# Sheet2.net
KiCad netlist of a schematic drawn in Altium Designer
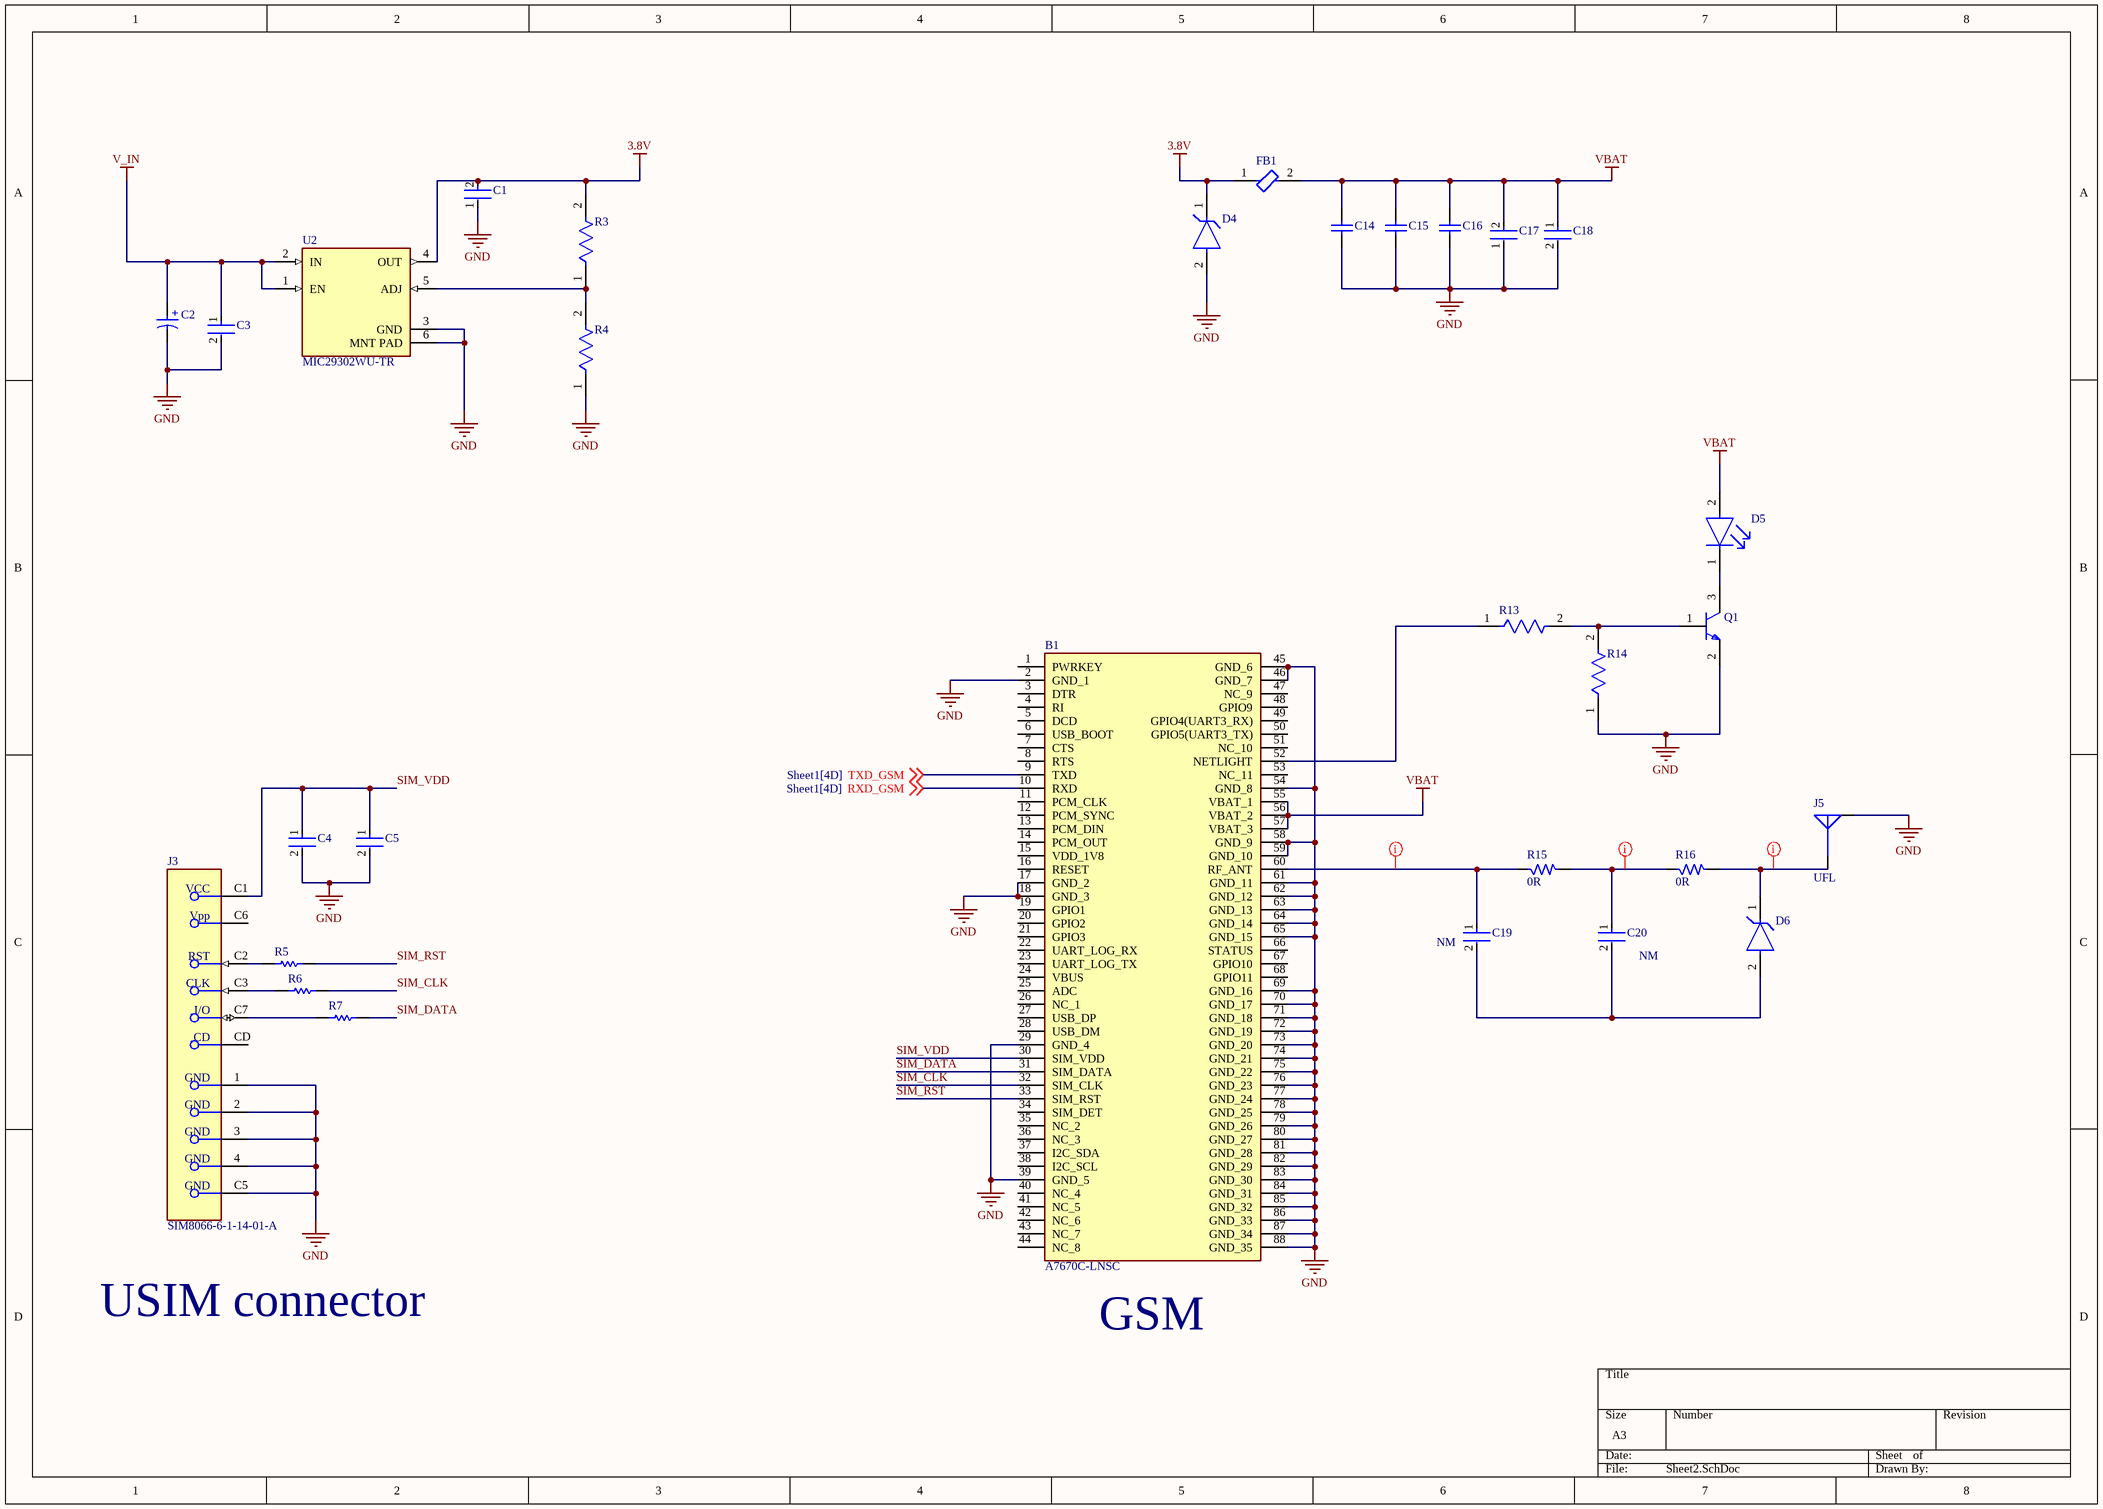
[diagram p0: Sheet2.SchDoc]

(export (version "E")
  (design (tool "Eeschema 10.0.6"))
  (components
    (comp (ref "B1")
      (value "A7670C-LNSC")
      (footprint "A7670CLNSC")
      (description "MODULE LTE CAT1")
      (libsource (lib "A7670C-LNSC") (part "A7670C-LNSC"))
    )
    (comp (ref "C1")
      (value "GRM155R71C104KA88D")
      (footprint "FP-GRM15-MFG")
      (description "CAP CER 0.1UF 16V X7R 0402")
      (fields
        (field (name "TOLERANCE") "10%")
        (field (name "OCTOPART") "https://octopart.com/grm155r71c104ka88d-murata-196880")
      )
      (libsource (lib "Altium Content Vault") (part "236180d848d6139a670b325ea6854c9"))
    )
    (comp (ref "C2")
      (value "865060653010")
      (footprint "WCAP-ASLL_D8H10.5")
      (fields (field (name "TOLERANCE") "20%"))
      (libsource (lib "Altium Content Vault") (part "Capacitor_Polarized"))
    )
    (comp (ref "C3")
      (value "C0402C105K8PACTU")
      (footprint "FP-C0402C105K8PACTU-MFG")
      (description "CAP CER 1UF 10V X5R 0402")
      (fields (field (name "VOLTAGE") "10V") (field (name "TOLERANCE") "10%"))
      (libsource (lib "Altium Content Vault") (part "11868f565c42a9108669ba33697ecf6"))
    )
    (comp (ref "C4")
      (value "C0402C104K4RACTU")
      (footprint "FP-C0402-BB-MFG")
      (description "CAP CER 0.1UF 16V X7R 0402")
      (fields
        (field (name "TOLERANCE") "0.1")
        (field (name "OCTOPART") "https://octopart.com/c0402c104k4ractu-kemet-94158")
      )
      (libsource (lib "Altium Content Vault") (part "b4654b650e69147ec39a6b967a45e02"))
    )
    (comp (ref "C5")
      (value "04025A330JAT2A")
      (footprint "FP-0402-L_1_0_1-W_0_5_0_1-IPC_A")
      (description "General Purpose Ceramic Capacitor, 0402, 33pF, 5%, C0G, 30ppm/°C, 50V")
      (fields (field (name "TOLERANCE") "5%") (field (name "VOLTAGE") "50V"))
      (libsource (lib "Altium Content Vault") (part "b4654b650e69147ec39a6b967a45e02"))
    )
    (comp (ref "C14")
      (value "GRM31CR60J107ME39L")
      (footprint "CAPC3216X190X55ML30T25")
      (description "Chip Capacitor, 100 uF, +/- 20%, 6.3 V, -55 to 85 degC, 1206 (3216 Metric), RoHS, Tape and Reel")
      (fields (field (name "TOLERANCE") "20%"))
      (libsource (lib "Altium Content Vault") (part "CAP-NP-2"))
    )
    (comp (ref "C15")
      (value "GRM31CR60J107ME39L")
      (footprint "CAPC3216X190X55ML30T25")
      (description "Chip Capacitor, 100 uF, +/- 20%, 6.3 V, -55 to 85 degC, 1206 (3216 Metric), RoHS, Tape and Reel")
      (fields (field (name "TOLERANCE") "20%"))
      (libsource (lib "Altium Content Vault") (part "CAP-NP-2"))
    )
    (comp (ref "C16")
      (value "GRM21BR71H105KA12L")
      (footprint "CAPC2013X135X45LL10T25")
      (fields (field (name "MANUFACTURER") "Murata"))
      (libsource (lib "Altium Content Vault") (part "CAP"))
    )
    (comp (ref "C17")
      (value "GRM155R71C104KA88D")
      (footprint "FP-GRM15-MFG")
      (description "CAP CER 0.1UF 16V X7R 0402")
      (fields
        (field (name "TOLERANCE") "10%")
        (field (name "OCTOPART") "https://octopart.com/grm155r71c104ka88d-murata-196880")
      )
      (libsource (lib "Altium Content Vault") (part "236180d848d6139a670b325ea6854c9"))
    )
    (comp (ref "C18")
      (value "CC0603JRNPO9BN330")
      (footprint "FP-CC0603-0_9-IPC_C")
      (description "CAP CER 33PF 50V C0G/NPO 0603")
      (fields (field (name "TOLERANCE") "5%") (field (name "VOLTAGE") "50V"))
      (libsource (lib "Altium Content Vault") (part "b4654b650e69147ec39a6b967a45e02"))
    )
    (comp (ref "C19")
      (value "04025C222KAT2A")
      (footprint "FP-0402-L_1_0_1-W_0_5_0_1-MFG")
      (description "General Purpose Ceramic Capacitor, 0402, 2.2nF, 10%, X7R, 15%, 50V")
      (fields (field (name "VOLTAGE") "50V") (field (name "TOLERANCE") "10%"))
      (libsource (lib "Altium Content Vault") (part "b4654b650e69147ec39a6b967a45e02"))
    )
    (comp (ref "C20")
      (value "C0402C104K4RACTU")
      (footprint "FP-C0402-BB-MFG")
      (description "CAP CER 0.1UF 16V X7R 0402")
      (fields
        (field (name "TOLERANCE") "0.1")
        (field (name "OCTOPART") "https://octopart.com/c0402c104k4ractu-kemet-94158")
      )
      (libsource (lib "Altium Content Vault") (part "b4654b650e69147ec39a6b967a45e02"))
    )
    (comp (ref "D4")
      (value "SMAJ6.0A")
      (footprint "FP-SMAJ-MFG")
      (description "TVS DIODE 6V 10.3V DO214AC")
      (fields
        (field (name "OCTOPART") "https://octopart.com/smaj6.0a-littelfuse-350212")
        (field (name "MANUFACTURER") "Littelfuse")
      )
      (libsource (lib "Altium Content Vault") (part "f813f71cba58e380607f5dd3caf9714"))
    )
    (comp (ref "D5")
      (value "LTST-C190GKT")
      (footprint "FP-LTST-C190GKT-MFG")
      (description "LED GREEN CLEAR CHIP SMD")
      (fields (field (name "VOLTAGE") "2V"))
      (libsource (lib "Altium Content Vault") (part "8706943c75ba83719d021d2fdc84c58"))
    )
    (comp (ref "D6")
      (value "SMAJ6.0A")
      (footprint "FP-SMAJ-MFG")
      (description "TVS DIODE 6V 10.3V DO214AC")
      (fields
        (field (name "OCTOPART") "https://octopart.com/smaj6.0a-littelfuse-350212")
        (field (name "MANUFACTURER") "Littelfuse")
      )
      (libsource (lib "Altium Content Vault") (part "f813f71cba58e380607f5dd3caf9714"))
    )
    (comp (ref "FB1")
      (value "BLM21PG300SN1D")
      (footprint "FP-BLM21-0_2-t0_85-e0_5-d-MFG")
      (description "Chip Ferrite Bead, 0805, 30Ω @ 100MHz, 0.014Ω, , 4A")
      (fields (field (name "TOLERANCE") "25%"))
      (libsource (lib "Altium Content Vault") (part "5f30dd21d616792df468990f7003faa"))
    )
    (comp (ref "J3")
      (value "SIM8066-6-1-14-01-A")
      (footprint "FP-SIM8066-6-1-14-01-A-MFG")
      (description "SIM8066-6-1-14-01-A Memory Card Connectors 1.44mm Nano SIM Conn w/Peg and Switch")
      (libsource (lib "Altium Content Vault") (part "1421b091a134f49a34fd3b08e40bfdd"))
    )
    (comp (ref "J5")
      (value "UFL")
      (footprint "MOLEX SD-734120110")
      (fields (field (name "PARTNUMBER") "MOLEX SD-734120110"))
      (libsource (lib "Conn RF") (part "UFL MOLEX SD-734120110"))
    )
    (comp (ref "Q1")
      (value "BC846B,215")
      (footprint "FP-SOT23-IPC_B")
      (description "TRANS NPN 65V 0.1A SOT23")
      (libsource (lib "Altium Content Vault") (part "4e2cbc3aa755f657dadd0993282992b"))
    )
    (comp (ref "R3")
      (value "CRCW0402100KFKED")
      (footprint "FP-CRCW0402-e3-IPC_C")
      (description "RES Thick Film, 100kΩ, 1%, 0.063W, 100ppm/°C, 0402")
      (fields (field (name "TOLERANCE") "1%"))
      (libsource (lib "Altium Content Vault") (part "1029c3af85768c4190bb7ad29bc67b5"))
    )
    (comp (ref "R4")
      (value "CRCW060347K0FKEA")
      (footprint "FP-CRCW0603-e3-IPC_B")
      (description "RES SMD 47K OHM 1% 1/10W 0603")
      (fields (field (name "TOLERANCE") "1%"))
      (libsource (lib "Altium Content Vault") (part "1029c3af85768c4190bb7ad29bc67b5"))
    )
    (comp (ref "R5")
      (value "CRCW040222R0FKED")
      (footprint "RESC1005X40X25LL05T05")
      (fields (field (name "MANUFACTURER") "Vishay Dale"))
      (libsource (lib "Altium Content Vault") (part "RES"))
    )
    (comp (ref "R6")
      (value "CRCW040222R0FKED")
      (footprint "RESC1005X40X25LL05T05")
      (fields (field (name "MANUFACTURER") "Vishay Dale"))
      (libsource (lib "Altium Content Vault") (part "RES"))
    )
    (comp (ref "R7")
      (value "CRCW040222R0FKED")
      (footprint "RESC1005X40X25LL05T05")
      (fields (field (name "MANUFACTURER") "Vishay Dale"))
      (libsource (lib "Altium Content Vault") (part "RES"))
    )
    (comp (ref "R13")
      (value "CRCW06034K70FKEA")
      (footprint "FP-CRCW0603-e3-IPC_A")
      (description "RES Thick Film, 4.7kΩ, 1%, 0.1W, 100ppm/°C, 0603")
      (fields (field (name "TOLERANCE") "1%"))
      (libsource (lib "Altium Content Vault") (part "1029c3af85768c4190bb7ad29bc67b5"))
    )
    (comp (ref "R14")
      (value "CRCW060347K0FKEA")
      (footprint "FP-CRCW0603-e3-IPC_B")
      (description "RES SMD 47K OHM 1% 1/10W 0603")
      (fields (field (name "TOLERANCE") "1%"))
      (libsource (lib "Altium Content Vault") (part "1029c3af85768c4190bb7ad29bc67b5"))
    )
    (comp (ref "R15")
      (value "0R")
      (footprint "RES_0805")
      (description "0 Ohms Jumper 0.125W, 1/8W Chip Resistor 0805 (2012 Metric) Automotive AEC-Q200 Thick Film")
      (fields (field (name "MANUFACTURER") "Walsin") (field (name "MANUFACTURER PART NUMBER") "WR08X000PTL"))
      (libsource (lib "ESTEEMPCBLIB") (part "RES_0R-0.125W-1%-0805"))
    )
    (comp (ref "R16")
      (value "0R")
      (footprint "RES_0805")
      (description "0 Ohms Jumper 0.125W, 1/8W Chip Resistor 0805 (2012 Metric) Automotive AEC-Q200 Thick Film")
      (fields (field (name "MANUFACTURER") "Walsin") (field (name "MANUFACTURER PART NUMBER") "WR08X000PTL"))
      (libsource (lib "ESTEEMPCBLIB") (part "RES_0R-0.125W-1%-0805"))
    )
    (comp (ref "U2")
      (value "MIC29302WU-TR")
      (footprint "FP-C04-012-MFG")
      (description "IC REG LINEAR POS ADJ 3A TO263-5")
      (fields
        (field (name "MANUFACTURER") "Microchip")
        (field (name "OCTOPART") "https://octopart.com/mic29302wu-tr-microchip-66801318")
      )
      (libsource (lib "Altium Content Vault") (part "0db40f55fda0e91d0d14528974a446d"))
    )
  )
  (nets
    (net (code "1") (name "/SIM_CLK") (class "Default")
      (node (ref "B1") (pin "32") (pinfunction "SIM_CLK_32") (pintype "passive"))
      (node (ref "R6") (pin "2") (pinfunction "2_2") (pintype "passive"))
    )
    (net (code "2") (name "/SIM_DATA") (class "Default")
      (node (ref "B1") (pin "31") (pinfunction "SIM_DATA_31") (pintype "passive"))
      (node (ref "R7") (pin "2") (pinfunction "2_2") (pintype "passive"))
    )
    (net (code "3") (name "/SIM_RST") (class "Default")
      (node (ref "B1") (pin "33") (pinfunction "SIM_RST_33") (pintype "passive"))
      (node (ref "R5") (pin "2") (pinfunction "2_2") (pintype "passive"))
    )
    (net (code "4") (name "/SIM_VDD") (class "Default")
      (node (ref "B1") (pin "30") (pinfunction "SIM_VDD_30") (pintype "passive"))
      (node (ref "C4") (pin "1") (pinfunction "1_1") (pintype "passive"))
      (node (ref "C5") (pin "1") (pinfunction "1_1") (pintype "passive"))
      (node (ref "J3") (pin "C1") (pinfunction "VCC_C1") (pintype "power_in"))
    )
    (net (code "5") (name "3.8V") (class "Default")
      (node (ref "C1") (pin "2") (pinfunction "2_2") (pintype "passive"))
      (node (ref "D4") (pin "1") (pinfunction "C_1") (pintype "passive"))
      (node (ref "FB1") (pin "1") (pinfunction "1_1") (pintype "passive"))
      (node (ref "R3") (pin "2") (pinfunction "2_2") (pintype "passive"))
      (node (ref "U2") (pin "4") (pinfunction "OUT_4") (pintype "output"))
    )
    (net (code "6") (name "GND") (class "Default")
      (node (ref "B1") (pin "17") (pinfunction "GND_2_17") (pintype "passive"))
      (node (ref "B1") (pin "18") (pinfunction "GND_3_18") (pintype "passive"))
      (node (ref "B1") (pin "2") (pinfunction "GND_1_2") (pintype "passive"))
      (node (ref "B1") (pin "29") (pinfunction "GND_4_29") (pintype "passive"))
      (node (ref "B1") (pin "39") (pinfunction "GND_5_39") (pintype "passive"))
      (node (ref "B1") (pin "45") (pinfunction "GND_6_45") (pintype "passive"))
      (node (ref "B1") (pin "46") (pinfunction "GND_7_46") (pintype "passive"))
      (node (ref "B1") (pin "54") (pinfunction "GND_8_54") (pintype "passive"))
      (node (ref "B1") (pin "58") (pinfunction "GND_9_58") (pintype "passive"))
      (node (ref "B1") (pin "59") (pinfunction "GND_10_59") (pintype "passive"))
      (node (ref "B1") (pin "61") (pinfunction "GND_11_61") (pintype "passive"))
      (node (ref "B1") (pin "62") (pinfunction "GND_12_62") (pintype "passive"))
      (node (ref "B1") (pin "63") (pinfunction "GND_13_63") (pintype "passive"))
      (node (ref "B1") (pin "64") (pinfunction "GND_14_64") (pintype "passive"))
      (node (ref "B1") (pin "65") (pinfunction "GND_15_65") (pintype "passive"))
      (node (ref "B1") (pin "69") (pinfunction "GND_16_69") (pintype "passive"))
      (node (ref "B1") (pin "70") (pinfunction "GND_17_70") (pintype "passive"))
      (node (ref "B1") (pin "71") (pinfunction "GND_18_71") (pintype "passive"))
      (node (ref "B1") (pin "72") (pinfunction "GND_19_72") (pintype "passive"))
      (node (ref "B1") (pin "73") (pinfunction "GND_20_73") (pintype "passive"))
      (node (ref "B1") (pin "74") (pinfunction "GND_21_74") (pintype "passive"))
      (node (ref "B1") (pin "75") (pinfunction "GND_22_75") (pintype "passive"))
      (node (ref "B1") (pin "76") (pinfunction "GND_23_76") (pintype "passive"))
      (node (ref "B1") (pin "77") (pinfunction "GND_24_77") (pintype "passive"))
      (node (ref "B1") (pin "78") (pinfunction "GND_25_78") (pintype "passive"))
      (node (ref "B1") (pin "79") (pinfunction "GND_26_79") (pintype "passive"))
      (node (ref "B1") (pin "80") (pinfunction "GND_27_80") (pintype "passive"))
      (node (ref "B1") (pin "81") (pinfunction "GND_28_81") (pintype "passive"))
      (node (ref "B1") (pin "82") (pinfunction "GND_29_82") (pintype "passive"))
      (node (ref "B1") (pin "83") (pinfunction "GND_30_83") (pintype "passive"))
      (node (ref "B1") (pin "84") (pinfunction "GND_31_84") (pintype "passive"))
      (node (ref "B1") (pin "85") (pinfunction "GND_32_85") (pintype "passive"))
      (node (ref "B1") (pin "86") (pinfunction "GND_33_86") (pintype "passive"))
      (node (ref "B1") (pin "87") (pinfunction "GND_34_87") (pintype "passive"))
      (node (ref "B1") (pin "88") (pinfunction "GND_35_88") (pintype "passive"))
      (node (ref "C1") (pin "1") (pinfunction "1_1") (pintype "passive"))
      (node (ref "C14") (pin "1") (pinfunction "1_1") (pintype "passive"))
      (node (ref "C15") (pin "1") (pinfunction "1_1") (pintype "passive"))
      (node (ref "C16") (pin "1") (pinfunction "1_1") (pintype "passive"))
      (node (ref "C17") (pin "1") (pinfunction "1_1") (pintype "passive"))
      (node (ref "C18") (pin "2") (pinfunction "2_2") (pintype "passive"))
      (node (ref "C2") (pin "2") (pinfunction "N_2") (pintype "passive"))
      (node (ref "C3") (pin "2") (pinfunction "2_2") (pintype "passive"))
      (node (ref "C4") (pin "2") (pinfunction "2_2") (pintype "passive"))
      (node (ref "C5") (pin "2") (pinfunction "2_2") (pintype "passive"))
      (node (ref "D4") (pin "2") (pinfunction "A_2") (pintype "passive"))
      (node (ref "J3") (pin "1") (pinfunction "GND_1") (pintype "power_in"))
      (node (ref "J3") (pin "2") (pinfunction "GND_2") (pintype "power_in"))
      (node (ref "J3") (pin "3") (pinfunction "GND_3") (pintype "power_in"))
      (node (ref "J3") (pin "4") (pinfunction "GND_4") (pintype "power_in"))
      (node (ref "J3") (pin "C5") (pinfunction "GND_C5") (pintype "power_in"))
      (node (ref "J5") (pin "G") (pinfunction "G_G") (pintype "passive"))
      (node (ref "Q1") (pin "2") (pinfunction "E_2") (pintype "passive"))
      (node (ref "R14") (pin "1") (pinfunction "1_1") (pintype "passive"))
      (node (ref "R4") (pin "1") (pinfunction "1_1") (pintype "passive"))
      (node (ref "U2") (pin "3") (pinfunction "GND_3") (pintype "power_in"))
      (node (ref "U2") (pin "6") (pinfunction "MNT_PAD_6") (pintype "passive"))
    )
    (net (code "7") (name "Net-(B1-NETLIGHT)") (class "Default")
      (node (ref "B1") (pin "52") (pinfunction "NETLIGHT_52") (pintype "passive"))
      (node (ref "R13") (pin "1") (pinfunction "1_1") (pintype "passive"))
    )
    (net (code "8") (name "Net-(B1-RF_ANT)") (class "Default")
      (node (ref "B1") (pin "60") (pinfunction "RF_ANT_60") (pintype "passive"))
      (node (ref "C19") (pin "1") (pinfunction "1_1") (pintype "passive"))
      (node (ref "R15") (pin "1") (pinfunction "1_1") (pintype "passive"))
    )
    (net (code "9") (name "Net-(C20-Pad1)") (class "Default")
      (node (ref "C20") (pin "1") (pinfunction "1_1") (pintype "passive"))
      (node (ref "R15") (pin "2") (pinfunction "2_2") (pintype "passive"))
      (node (ref "R16") (pin "1") (pinfunction "1_1") (pintype "passive"))
    )
    (net (code "10") (name "Net-(D5-C)") (class "Default")
      (node (ref "D5") (pin "1") (pinfunction "C_1") (pintype "passive"))
      (node (ref "Q1") (pin "3") (pinfunction "C_3") (pintype "passive"))
    )
    (net (code "11") (name "Net-(D6-A)") (class "Default")
      (node (ref "C19") (pin "2") (pinfunction "2_2") (pintype "passive"))
      (node (ref "C20") (pin "2") (pinfunction "2_2") (pintype "passive"))
      (node (ref "D6") (pin "2") (pinfunction "A_2") (pintype "passive"))
    )
    (net (code "12") (name "Net-(D6-C)") (class "Default")
      (node (ref "D6") (pin "1") (pinfunction "C_1") (pintype "passive"))
      (node (ref "J5") (pin "S") (pinfunction "S_S") (pintype "passive"))
      (node (ref "R16") (pin "2") (pinfunction "2_2") (pintype "passive"))
    )
    (net (code "13") (name "Net-(J3-CLK)") (class "Default")
      (node (ref "J3") (pin "C3") (pinfunction "CLK_C3") (pintype "input"))
      (node (ref "R6") (pin "1") (pinfunction "1_1") (pintype "passive"))
    )
    (net (code "14") (name "Net-(J3-I{slash}O)") (class "Default")
      (node (ref "J3") (pin "C7") (pinfunction "I/O_C7") (pintype "bidirectional"))
      (node (ref "R7") (pin "1") (pinfunction "1_1") (pintype "passive"))
    )
    (net (code "15") (name "Net-(J3-RST)") (class "Default")
      (node (ref "J3") (pin "C2") (pinfunction "RST_C2") (pintype "input"))
      (node (ref "R5") (pin "1") (pinfunction "1_1") (pintype "passive"))
    )
    (net (code "16") (name "Net-(Q1-B)") (class "Default")
      (node (ref "Q1") (pin "1") (pinfunction "B_1") (pintype "passive"))
      (node (ref "R13") (pin "2") (pinfunction "2_2") (pintype "passive"))
      (node (ref "R14") (pin "2") (pinfunction "2_2") (pintype "passive"))
    )
    (net (code "17") (name "Net-(U2-ADJ)") (class "Default")
      (node (ref "R3") (pin "1") (pinfunction "1_1") (pintype "passive"))
      (node (ref "R4") (pin "2") (pinfunction "2_2") (pintype "passive"))
      (node (ref "U2") (pin "5") (pinfunction "ADJ_5") (pintype "input"))
    )
    (net (code "18") (name "RXD_GSM") (class "Default")
      (node (ref "B1") (pin "10") (pinfunction "RXD_10") (pintype "passive"))
    )
    (net (code "19") (name "TXD_GSM") (class "Default")
      (node (ref "B1") (pin "9") (pinfunction "TXD_9") (pintype "passive"))
    )
    (net (code "20") (name "VBAT") (class "Default")
      (node (ref "B1") (pin "55") (pinfunction "VBAT_1_55") (pintype "passive"))
      (node (ref "B1") (pin "56") (pinfunction "VBAT_2_56") (pintype "passive"))
      (node (ref "B1") (pin "57") (pinfunction "VBAT_3_57") (pintype "passive"))
      (node (ref "C14") (pin "2") (pinfunction "2_2") (pintype "passive"))
      (node (ref "C15") (pin "2") (pinfunction "2_2") (pintype "passive"))
      (node (ref "C16") (pin "2") (pinfunction "2_2") (pintype "passive"))
      (node (ref "C17") (pin "2") (pinfunction "2_2") (pintype "passive"))
      (node (ref "C18") (pin "1") (pinfunction "1_1") (pintype "passive"))
      (node (ref "D5") (pin "2") (pinfunction "A_2") (pintype "passive"))
      (node (ref "FB1") (pin "2") (pinfunction "2_2") (pintype "passive"))
    )
    (net (code "21") (name "V_IN") (class "Default")
      (node (ref "C2") (pin "1") (pinfunction "P_1") (pintype "passive"))
      (node (ref "C3") (pin "1") (pinfunction "1_1") (pintype "passive"))
      (node (ref "U2") (pin "1") (pinfunction "EN_1") (pintype "input"))
      (node (ref "U2") (pin "2") (pinfunction "IN_2") (pintype "input"))
    )
    (net (code "22") (name "unconnected-(B1-ADC-Pad25)") (class "Default")
      (node (ref "B1") (pin "25") (pinfunction "ADC_25") (pintype "passive"))
    )
    (net (code "23") (name "unconnected-(B1-CTS-Pad7)") (class "Default")
      (node (ref "B1") (pin "7") (pinfunction "CTS_7") (pintype "passive"))
    )
    (net (code "24") (name "unconnected-(B1-DCD-Pad5)") (class "Default")
      (node (ref "B1") (pin "5") (pinfunction "DCD_5") (pintype "passive"))
    )
    (net (code "25") (name "unconnected-(B1-DTR-Pad3)") (class "Default")
      (node (ref "B1") (pin "3") (pinfunction "DTR_3") (pintype "passive"))
    )
    (net (code "26") (name "unconnected-(B1-GPIO1-Pad19)") (class "Default")
      (node (ref "B1") (pin "19") (pinfunction "GPIO1_19") (pintype "passive"))
    )
    (net (code "27") (name "unconnected-(B1-GPIO2-Pad20)") (class "Default")
      (node (ref "B1") (pin "20") (pinfunction "GPIO2_20") (pintype "passive"))
    )
    (net (code "28") (name "unconnected-(B1-GPIO3-Pad21)") (class "Default")
      (node (ref "B1") (pin "21") (pinfunction "GPIO3_21") (pintype "passive"))
    )
    (net (code "29") (name "unconnected-(B1-GPIO4(UART3_RX)-Pad49)") (class "Default")
      (node (ref "B1") (pin "49") (pinfunction "GPIO4(UART3_RX)_49") (pintype "passive"))
    )
    (net (code "30") (name "unconnected-(B1-GPIO5(UART3_TX)-Pad50)") (class "Default")
      (node (ref "B1") (pin "50") (pinfunction "GPIO5(UART3_TX)_50") (pintype "passive"))
    )
    (net (code "31") (name "unconnected-(B1-GPIO9-Pad48)") (class "Default")
      (node (ref "B1") (pin "48") (pinfunction "GPIO9_48") (pintype "passive"))
    )
    (net (code "32") (name "unconnected-(B1-GPIO10-Pad67)") (class "Default")
      (node (ref "B1") (pin "67") (pinfunction "GPIO10_67") (pintype "passive"))
    )
    (net (code "33") (name "unconnected-(B1-GPIO11-Pad68)") (class "Default")
      (node (ref "B1") (pin "68") (pinfunction "GPIO11_68") (pintype "passive"))
    )
    (net (code "34") (name "unconnected-(B1-I2C_SCL-Pad38)") (class "Default")
      (node (ref "B1") (pin "38") (pinfunction "I2C_SCL_38") (pintype "passive"))
    )
    (net (code "35") (name "unconnected-(B1-I2C_SDA-Pad37)") (class "Default")
      (node (ref "B1") (pin "37") (pinfunction "I2C_SDA_37") (pintype "passive"))
    )
    (net (code "36") (name "unconnected-(B1-NC_1-Pad26)") (class "Default")
      (node (ref "B1") (pin "26") (pinfunction "NC_1_26") (pintype "passive"))
    )
    (net (code "37") (name "unconnected-(B1-NC_2-Pad35)") (class "Default")
      (node (ref "B1") (pin "35") (pinfunction "NC_2_35") (pintype "passive"))
    )
    (net (code "38") (name "unconnected-(B1-NC_3-Pad36)") (class "Default")
      (node (ref "B1") (pin "36") (pinfunction "NC_3_36") (pintype "passive"))
    )
    (net (code "39") (name "unconnected-(B1-NC_4-Pad40)") (class "Default")
      (node (ref "B1") (pin "40") (pinfunction "NC_4_40") (pintype "passive"))
    )
    (net (code "40") (name "unconnected-(B1-NC_5-Pad41)") (class "Default")
      (node (ref "B1") (pin "41") (pinfunction "NC_5_41") (pintype "passive"))
    )
    (net (code "41") (name "unconnected-(B1-NC_6-Pad42)") (class "Default")
      (node (ref "B1") (pin "42") (pinfunction "NC_6_42") (pintype "passive"))
    )
    (net (code "42") (name "unconnected-(B1-NC_7-Pad43)") (class "Default")
      (node (ref "B1") (pin "43") (pinfunction "NC_7_43") (pintype "passive"))
    )
    (net (code "43") (name "unconnected-(B1-NC_8-Pad44)") (class "Default")
      (node (ref "B1") (pin "44") (pinfunction "NC_8_44") (pintype "passive"))
    )
    (net (code "44") (name "unconnected-(B1-NC_9-Pad47)") (class "Default")
      (node (ref "B1") (pin "47") (pinfunction "NC_9_47") (pintype "passive"))
    )
    (net (code "45") (name "unconnected-(B1-NC_10-Pad51)") (class "Default")
      (node (ref "B1") (pin "51") (pinfunction "NC_10_51") (pintype "passive"))
    )
    (net (code "46") (name "unconnected-(B1-NC_11-Pad53)") (class "Default")
      (node (ref "B1") (pin "53") (pinfunction "NC_11_53") (pintype "passive"))
    )
    (net (code "47") (name "unconnected-(B1-PCM_CLK-Pad11)") (class "Default")
      (node (ref "B1") (pin "11") (pinfunction "PCM_CLK_11") (pintype "passive"))
    )
    (net (code "48") (name "unconnected-(B1-PCM_DIN-Pad13)") (class "Default")
      (node (ref "B1") (pin "13") (pinfunction "PCM_DIN_13") (pintype "passive"))
    )
    (net (code "49") (name "unconnected-(B1-PCM_OUT-Pad14)") (class "Default")
      (node (ref "B1") (pin "14") (pinfunction "PCM_OUT_14") (pintype "passive"))
    )
    (net (code "50") (name "unconnected-(B1-PCM_SYNC-Pad12)") (class "Default")
      (node (ref "B1") (pin "12") (pinfunction "PCM_SYNC_12") (pintype "passive"))
    )
    (net (code "51") (name "unconnected-(B1-PWRKEY-Pad1)") (class "Default")
      (node (ref "B1") (pin "1") (pinfunction "PWRKEY_1") (pintype "passive"))
    )
    (net (code "52") (name "unconnected-(B1-RESET-Pad16)") (class "Default")
      (node (ref "B1") (pin "16") (pinfunction "RESET_16") (pintype "passive"))
    )
    (net (code "53") (name "unconnected-(B1-RI-Pad4)") (class "Default")
      (node (ref "B1") (pin "4") (pinfunction "RI_4") (pintype "passive"))
    )
    (net (code "54") (name "unconnected-(B1-RTS-Pad8)") (class "Default")
      (node (ref "B1") (pin "8") (pinfunction "RTS_8") (pintype "passive"))
    )
    (net (code "55") (name "unconnected-(B1-SIM_DET-Pad34)") (class "Default")
      (node (ref "B1") (pin "34") (pinfunction "SIM_DET_34") (pintype "passive"))
    )
    (net (code "56") (name "unconnected-(B1-STATUS-Pad66)") (class "Default")
      (node (ref "B1") (pin "66") (pinfunction "STATUS_66") (pintype "passive"))
    )
    (net (code "57") (name "unconnected-(B1-UART_LOG_RX-Pad22)") (class "Default")
      (node (ref "B1") (pin "22") (pinfunction "UART_LOG_RX_22") (pintype "passive"))
    )
    (net (code "58") (name "unconnected-(B1-UART_LOG_TX-Pad23)") (class "Default")
      (node (ref "B1") (pin "23") (pinfunction "UART_LOG_TX_23") (pintype "passive"))
    )
    (net (code "59") (name "unconnected-(B1-USB_BOOT-Pad6)") (class "Default")
      (node (ref "B1") (pin "6") (pinfunction "USB_BOOT_6") (pintype "passive"))
    )
    (net (code "60") (name "unconnected-(B1-USB_DM-Pad28)") (class "Default")
      (node (ref "B1") (pin "28") (pinfunction "USB_DM_28") (pintype "passive"))
    )
    (net (code "61") (name "unconnected-(B1-USB_DP-Pad27)") (class "Default")
      (node (ref "B1") (pin "27") (pinfunction "USB_DP_27") (pintype "passive"))
    )
    (net (code "62") (name "unconnected-(B1-VBUS-Pad24)") (class "Default")
      (node (ref "B1") (pin "24") (pinfunction "VBUS_24") (pintype "passive"))
    )
    (net (code "63") (name "unconnected-(B1-VDD_1V8-Pad15)") (class "Default")
      (node (ref "B1") (pin "15") (pinfunction "VDD_1V8_15") (pintype "passive"))
    )
    (net (code "64") (name "unconnected-(J3-PadCD)") (class "Default")
      (node (ref "J3") (pin "CD") (pinfunction "CD_CD") (pintype "passive"))
    )
    (net (code "65") (name "unconnected-(J3-Vpp-PadC6)") (class "Default")
      (node (ref "J3") (pin "C6") (pinfunction "Vpp_C6") (pintype "power_in"))
    )
  )
)
